# wirelessnode_triac.net
KiCad netlist of a schematic drawn in EAGLE
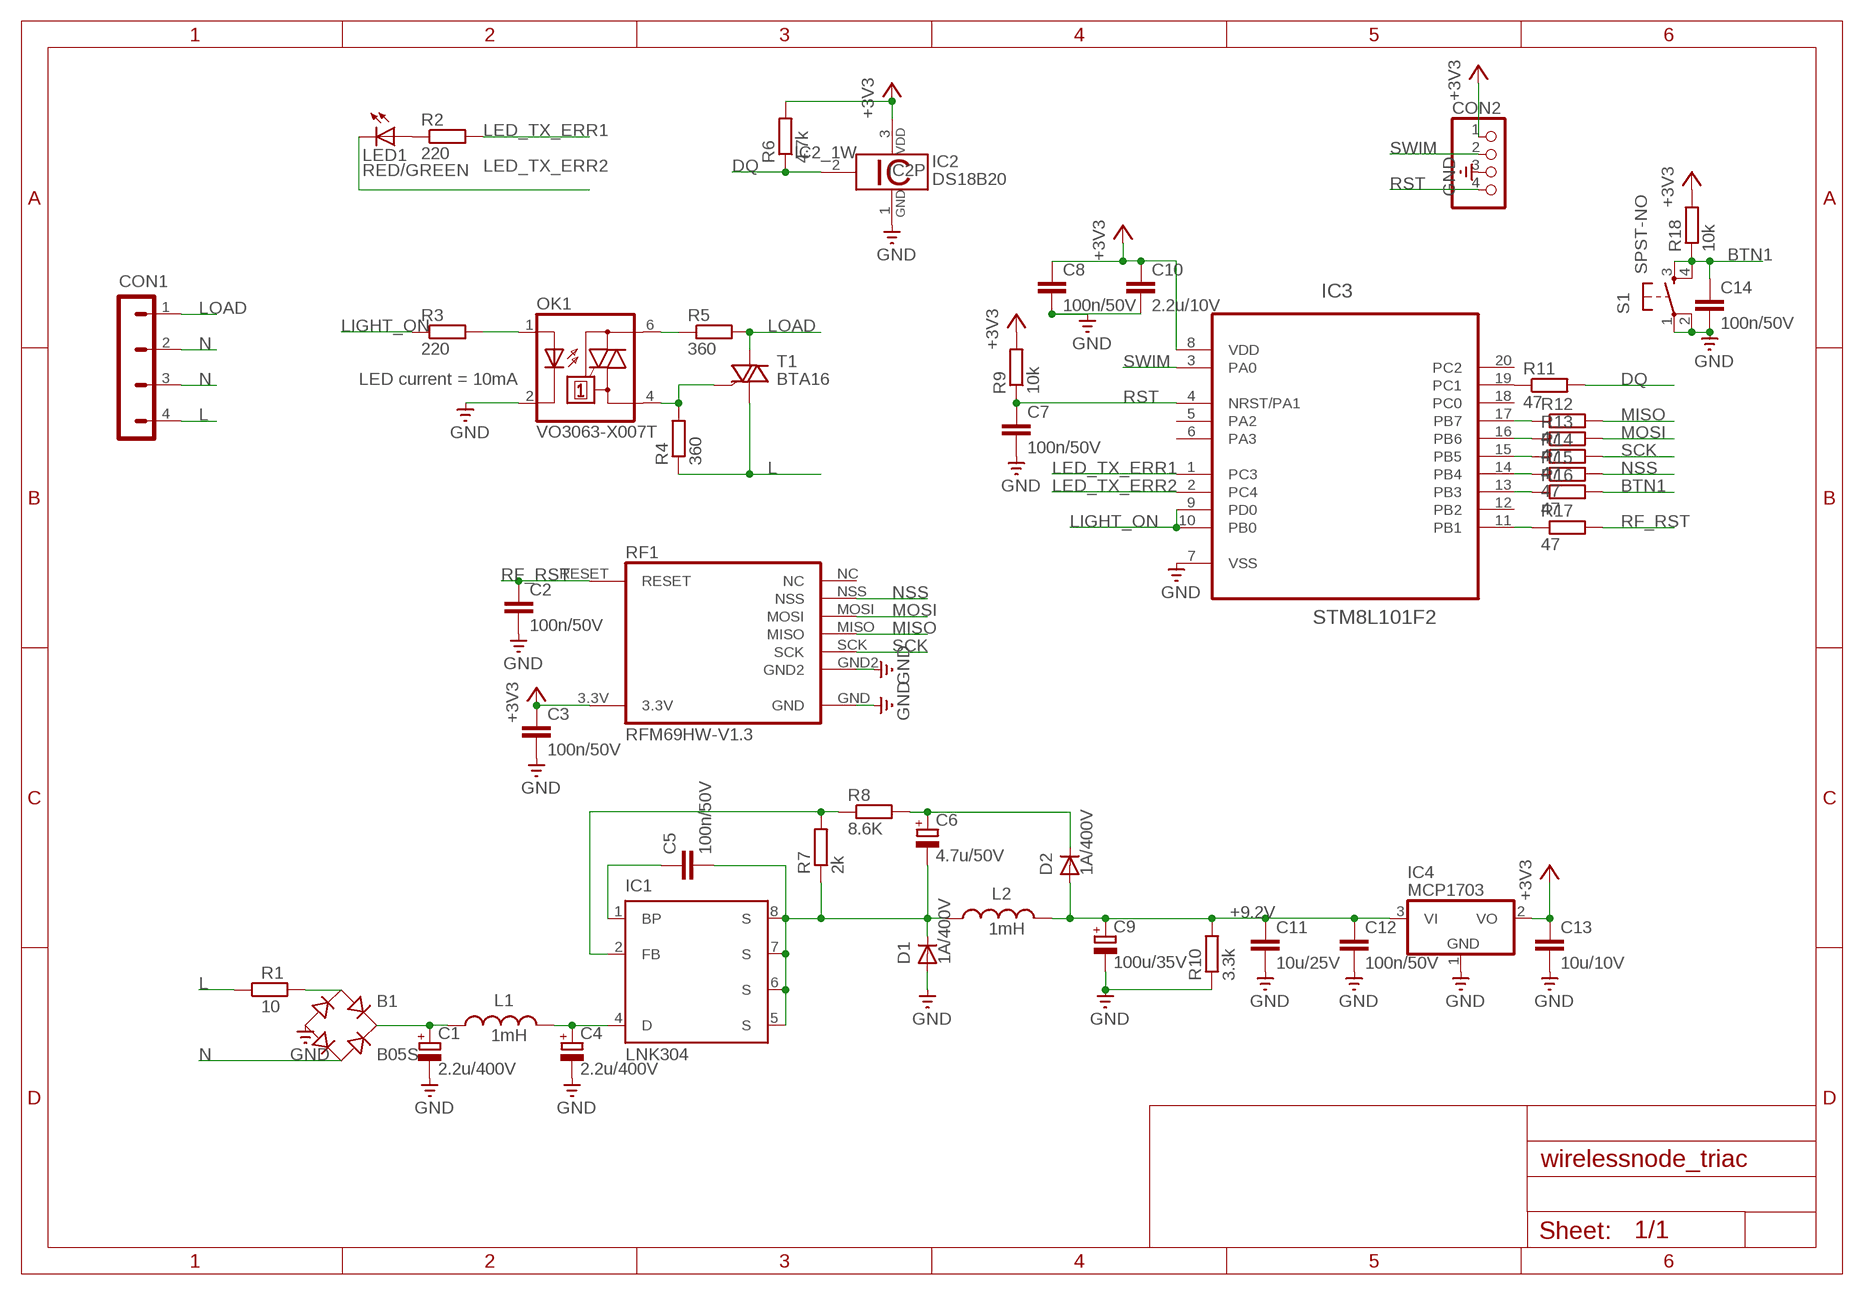
[diagram p0: schematic, sheet 1]

(export (version "E")
  (design (tool "Eeschema 10.0.6"))
  (components
    (comp (ref "B1")
      (value "B05S")
      (footprint "eagle-import:MBS")
      (libsource (lib "eagle-import") (part "BS05"))
    )
    (comp (ref "C1")
      (value "2.2u/400V")
      (footprint "eagle-import:E3.5-8")
      (libsource (lib "eagle-import") (part "C-POL-EUE3.5-8"))
    )
    (comp (ref "C2")
      (value "100n/50V")
      (footprint "eagle-import:C0603K")
      (libsource (lib "eagle-import") (part "C-EUC0603K"))
    )
    (comp (ref "C3")
      (value "100n/50V")
      (footprint "eagle-import:C0603K")
      (libsource (lib "eagle-import") (part "C-EUC0603K"))
    )
    (comp (ref "C4")
      (value "2.2u/400V")
      (footprint "eagle-import:E3.5-8")
      (libsource (lib "eagle-import") (part "C-POL-EUE3.5-8"))
    )
    (comp (ref "C5")
      (value "100n/50V")
      (footprint "eagle-import:C0603K")
      (libsource (lib "eagle-import") (part "C-EUC0603K"))
    )
    (comp (ref "C6")
      (value "4.7u/50V")
      (footprint "eagle-import:PANASONIC_C_LARGER_PADS")
      (libsource (lib "eagle-import") (part "C-POL-EU"))
    )
    (comp (ref "C7")
      (value "100n/50V")
      (footprint "eagle-import:C0603K")
      (libsource (lib "eagle-import") (part "C-EUC0603K"))
    )
    (comp (ref "C8")
      (value "100n/50V")
      (footprint "eagle-import:C0603K")
      (libsource (lib "eagle-import") (part "C-EUC0603K"))
    )
    (comp (ref "C9")
      (value "100u/35V")
      (footprint "eagle-import:PANASONIC_D_LARGER_PADS")
      (libsource (lib "eagle-import") (part "C-POL-EUPANASONIC_D"))
    )
    (comp (ref "C10")
      (value "2.2u/10V")
      (footprint "eagle-import:C0603K")
      (libsource (lib "eagle-import") (part "C-EUC0603K"))
    )
    (comp (ref "C11")
      (value "10u/25V")
      (footprint "eagle-import:C1206")
      (libsource (lib "eagle-import") (part "C-EUC1206"))
    )
    (comp (ref "C12")
      (value "100n/50V")
      (footprint "eagle-import:C0603K")
      (libsource (lib "eagle-import") (part "C-EUC0603K"))
    )
    (comp (ref "C13")
      (value "10u/10V")
      (footprint "eagle-import:C0603K")
      (libsource (lib "eagle-import") (part "C-EUC0603K"))
    )
    (comp (ref "C14")
      (value "100n/50V")
      (footprint "eagle-import:C0603K")
      (libsource (lib "eagle-import") (part "C-EUC0603K"))
    )
    (comp (ref "CON1")
      (value "POWER_CONN_4")
      (footprint "eagle-import:TERMINAL_BLOCK_4")
      (libsource (lib "eagle-import") (part "POWER_CONN_4"))
    )
    (comp (ref "CON2")
      (value "ZL321-4P")
      (footprint "eagle-import:CON_1X4_1.27_SMD")
      (libsource (lib "eagle-import") (part "CON_1X4PIN_1.27MM_SMD"))
    )
    (comp (ref "D1")
      (value "1A/400V")
      (footprint "eagle-import:DO214-AC")
      (libsource (lib "eagle-import") (part "US1G-DIO"))
    )
    (comp (ref "D2")
      (value "1A/400V")
      (footprint "eagle-import:SOD-123F")
      (libsource (lib "eagle-import") (part "SL1G"))
    )
    (comp (ref "IC1")
      (value "LNK304")
      (footprint "eagle-import:SO8_NO_PIN3")
      (libsource (lib "eagle-import") (part "LNK304"))
    )
    (comp (ref "IC2")
      (value "DS18B20")
      (footprint "eagle-import:TO92-")
      (libsource (lib "eagle-import") (part "DS18B20"))
    )
    (comp (ref "IC3")
      (value "STM8L101F2")
      (footprint "eagle-import:TSSOP20")
      (libsource (lib "eagle-import") (part "STM8L101F2"))
    )
    (comp (ref "IC4")
      (value "MCP1703")
      (footprint "eagle-import:SOT23")
      (libsource (lib "eagle-import") (part "MCP1703CB"))
    )
    (comp (ref "L1")
      (value "1mH")
      (footprint "eagle-import:DE0703")
      (libsource (lib "eagle-import") (part "FERROCORE_DE0703-1000"))
    )
    (comp (ref "L2")
      (value "1mH")
      (footprint "eagle-import:DE0703")
      (libsource (lib "eagle-import") (part "FERROCORE_DE0703-1000"))
    )
    (comp (ref "LED1")
      (value "RED/GREEN")
      (footprint "eagle-import:LED5MM")
      (libsource (lib "eagle-import") (part "LED5MM"))
    )
    (comp (ref "OK1")
      (value "VO3063-X007T")
      (footprint "eagle-import:DIL6-SMD")
      (fields (field (name "MF") "FAIRCHILD SEMICONDUCTOR") (field (name "MPN") "MOC3042SM"))
      (libsource (lib "eagle-import") (part "MOC30S42"))
    )
    (comp (ref "R1")
      (value "10")
      (footprint "eagle-import:CF1WS")
      (libsource (lib "eagle-import") (part "R_CF1WS"))
    )
    (comp (ref "R2")
      (value "220")
      (footprint "eagle-import:R0603")
      (libsource (lib "eagle-import") (part "R-EU_R0603"))
    )
    (comp (ref "R3")
      (value "220")
      (footprint "eagle-import:R0603")
      (libsource (lib "eagle-import") (part "R-EU_R0603"))
    )
    (comp (ref "R4")
      (value "360")
      (footprint "eagle-import:R0603")
      (libsource (lib "eagle-import") (part "R-EU_R0603"))
    )
    (comp (ref "R5")
      (value "360")
      (footprint "eagle-import:R0603")
      (libsource (lib "eagle-import") (part "R-EU_R0603"))
    )
    (comp (ref "R6")
      (value "4.7k")
      (footprint "eagle-import:R0603")
      (libsource (lib "eagle-import") (part "R-EU_R0603"))
    )
    (comp (ref "R7")
      (value "2k")
      (footprint "eagle-import:R0603")
      (libsource (lib "eagle-import") (part "R-EU_R0603"))
    )
    (comp (ref "R8")
      (value "8.6K")
      (footprint "eagle-import:R0603")
      (libsource (lib "eagle-import") (part "R-EU_R0603"))
    )
    (comp (ref "R9")
      (value "10k")
      (footprint "eagle-import:R0603")
      (libsource (lib "eagle-import") (part "R-EU_R0603"))
    )
    (comp (ref "R10")
      (value "3.3k")
      (footprint "eagle-import:R0603")
      (libsource (lib "eagle-import") (part "R-EU_R0603"))
    )
    (comp (ref "R11")
      (value "47")
      (footprint "eagle-import:R0603")
      (libsource (lib "eagle-import") (part "R-EU_R0603"))
    )
    (comp (ref "R12")
      (value "47")
      (footprint "eagle-import:R0603")
      (libsource (lib "eagle-import") (part "R-EU_R0603"))
    )
    (comp (ref "R13")
      (value "47")
      (footprint "eagle-import:R0603")
      (libsource (lib "eagle-import") (part "R-EU_R0603"))
    )
    (comp (ref "R14")
      (value "47")
      (footprint "eagle-import:R0603")
      (libsource (lib "eagle-import") (part "R-EU_R0603"))
    )
    (comp (ref "R15")
      (value "47")
      (footprint "eagle-import:R0603")
      (libsource (lib "eagle-import") (part "R-EU_R0603"))
    )
    (comp (ref "R16")
      (value "47")
      (footprint "eagle-import:R0603")
      (libsource (lib "eagle-import") (part "R-EU_R0603"))
    )
    (comp (ref "R17")
      (value "47")
      (footprint "eagle-import:R0603")
      (libsource (lib "eagle-import") (part "R-EU_R0603"))
    )
    (comp (ref "R18")
      (value "10k")
      (footprint "eagle-import:R0603")
      (libsource (lib "eagle-import") (part "R-EU_R0603"))
    )
    (comp (ref "RF1")
      (value "RFM69HW-V1.3")
      (footprint "eagle-import:RFM69HW-V1.3-SMD")
      (libsource (lib "eagle-import") (part "RFM69HW-V1.3"))
    )
    (comp (ref "S1")
      (value "SPST-NO")
      (footprint "eagle-import:DTSM-63X-V-7MM_HEIGHT")
      (libsource (lib "eagle-import") (part "DTSM-63X-V"))
    )
    (comp (ref "T1")
      (value "BTA16")
      (footprint "eagle-import:TO220_SMD")
      (libsource (lib "eagle-import") (part "BT136SMD"))
    )
  )
  (nets
    (net (code "1") (name "+3V3") (class "Default")
      (node (ref "C10") (pin "1") (pinfunction "1_1") (pintype "passive"))
      (node (ref "C13") (pin "1") (pinfunction "1_1") (pintype "passive"))
      (node (ref "C3") (pin "1") (pinfunction "1_1") (pintype "passive"))
      (node (ref "C8") (pin "1") (pinfunction "1_1") (pintype "passive"))
      (node (ref "CON2") (pin "1") (pinfunction "1_1") (pintype "passive"))
      (node (ref "IC2") (pin "3") (pinfunction "VDD_3") (pintype "power_in"))
      (node (ref "IC3") (pin "8") (pinfunction "VDD_8") (pintype "power_in"))
      (node (ref "IC4") (pin "2") (pinfunction "VO_2") (pintype "passive"))
      (node (ref "R18") (pin "2") (pinfunction "2_2") (pintype "passive"))
      (node (ref "R6") (pin "2") (pinfunction "2_2") (pintype "passive"))
      (node (ref "R9") (pin "2") (pinfunction "2_2") (pintype "passive"))
      (node (ref "RF1") (pin "3.3V") (pinfunction "3.3V_3.3V") (pintype "power_in"))
    )
    (net (code "2") (name "/+9.2V") (class "Default")
      (node (ref "C11") (pin "1") (pinfunction "1_1") (pintype "passive"))
      (node (ref "C12") (pin "1") (pinfunction "1_1") (pintype "passive"))
      (node (ref "C9") (pin "+") (pinfunction "+_+") (pintype "passive"))
      (node (ref "D2") (pin "2") (pinfunction "A_2") (pintype "passive"))
      (node (ref "IC4") (pin "3") (pinfunction "VI_3") (pintype "input"))
      (node (ref "L2") (pin "P$2") (pinfunction "2_P$2") (pintype "passive"))
      (node (ref "R10") (pin "2") (pinfunction "2_2") (pintype "passive"))
    )
    (net (code "3") (name "/BTN1") (class "Default")
      (node (ref "C14") (pin "1") (pinfunction "1_1") (pintype "passive"))
      (node (ref "R16") (pin "2") (pinfunction "2_2") (pintype "passive"))
      (node (ref "R18") (pin "1") (pinfunction "1_1") (pintype "passive"))
      (node (ref "S1") (pin "3") (pinfunction "S_3") (pintype "passive"))
      (node (ref "S1") (pin "4") (pinfunction "S1_4") (pintype "passive"))
    )
    (net (code "4") (name "/DQ") (class "Default")
      (node (ref "IC2") (pin "2") (pinfunction "1W_2") (pintype "power_in"))
      (node (ref "R11") (pin "2") (pinfunction "2_2") (pintype "passive"))
      (node (ref "R6") (pin "1") (pinfunction "1_1") (pintype "passive"))
    )
    (net (code "5") (name "/L") (class "Default")
      (node (ref "CON1") (pin "4") (pinfunction "P$4_4") (pintype "bidirectional"))
      (node (ref "R1") (pin "1") (pinfunction "1_1") (pintype "passive"))
      (node (ref "R4") (pin "1") (pinfunction "1_1") (pintype "passive"))
      (node (ref "T1") (pin "1") (pinfunction "A1_1") (pintype "passive"))
    )
    (net (code "6") (name "/LED_TX_ERR1") (class "Default")
      (node (ref "IC3") (pin "1") (pinfunction "PC3_1") (pintype "bidirectional"))
      (node (ref "R2") (pin "2") (pinfunction "2_2") (pintype "passive"))
    )
    (net (code "7") (name "/LED_TX_ERR2") (class "Default")
      (node (ref "IC3") (pin "2") (pinfunction "PC4_2") (pintype "bidirectional"))
      (node (ref "LED1") (pin "K") (pinfunction "C_K") (pintype "passive"))
    )
    (net (code "8") (name "/LIGHT_ON") (class "Default")
      (node (ref "IC3") (pin "10") (pinfunction "PB0_10") (pintype "bidirectional"))
      (node (ref "IC3") (pin "9") (pinfunction "PD0_9") (pintype "bidirectional"))
      (node (ref "R3") (pin "1") (pinfunction "1_1") (pintype "passive"))
    )
    (net (code "9") (name "/LOAD") (class "Default")
      (node (ref "CON1") (pin "1") (pinfunction "P$1_1") (pintype "bidirectional"))
      (node (ref "R5") (pin "2") (pinfunction "2_2") (pintype "passive"))
      (node (ref "T1") (pin "2") (pinfunction "A2_2") (pintype "passive"))
    )
    (net (code "10") (name "/MISO") (class "Default")
      (node (ref "R12") (pin "2") (pinfunction "2_2") (pintype "passive"))
      (node (ref "RF1") (pin "MISO") (pinfunction "MISO_MISO") (pintype "output"))
    )
    (net (code "11") (name "/MOSI") (class "Default")
      (node (ref "R13") (pin "2") (pinfunction "2_2") (pintype "passive"))
      (node (ref "RF1") (pin "MOSI") (pinfunction "MOSI_MOSI") (pintype "output"))
    )
    (net (code "12") (name "/N") (class "Default")
      (node (ref "B1") (pin "AC2") (pinfunction "AC2_AC2") (pintype "passive"))
      (node (ref "CON1") (pin "2") (pinfunction "P$2_2") (pintype "bidirectional"))
      (node (ref "CON1") (pin "3") (pinfunction "P$3_3") (pintype "bidirectional"))
    )
    (net (code "13") (name "/NSS") (class "Default")
      (node (ref "R15") (pin "2") (pinfunction "2_2") (pintype "passive"))
      (node (ref "RF1") (pin "NSS") (pinfunction "NSS_NSS") (pintype "output"))
    )
    (net (code "14") (name "/RF_RST") (class "Default")
      (node (ref "C2") (pin "1") (pinfunction "1_1") (pintype "passive"))
      (node (ref "R17") (pin "2") (pinfunction "2_2") (pintype "passive"))
      (node (ref "RF1") (pin "RESET") (pinfunction "RESET_RESET") (pintype "power_in"))
    )
    (net (code "15") (name "/RST") (class "Default")
      (node (ref "C7") (pin "1") (pinfunction "1_1") (pintype "passive"))
      (node (ref "CON2") (pin "4") (pinfunction "4_4") (pintype "passive"))
      (node (ref "IC3") (pin "4") (pinfunction "NRST/PA1_4") (pintype "bidirectional"))
      (node (ref "R9") (pin "1") (pinfunction "1_1") (pintype "passive"))
    )
    (net (code "16") (name "/SCK") (class "Default")
      (node (ref "R14") (pin "2") (pinfunction "2_2") (pintype "passive"))
      (node (ref "RF1") (pin "SCK") (pinfunction "SCK_SCK") (pintype "output"))
    )
    (net (code "17") (name "/SWIM") (class "Default")
      (node (ref "CON2") (pin "2") (pinfunction "2_2") (pintype "passive"))
      (node (ref "IC3") (pin "3") (pinfunction "PA0_3") (pintype "power_in"))
    )
    (net (code "18") (name "GND") (class "Default")
      (node (ref "B1") (pin "-") (pinfunction "-_-") (pintype "passive"))
      (node (ref "C1") (pin "-") (pinfunction "-_-") (pintype "passive"))
      (node (ref "C10") (pin "2") (pinfunction "2_2") (pintype "passive"))
      (node (ref "C11") (pin "2") (pinfunction "2_2") (pintype "passive"))
      (node (ref "C12") (pin "2") (pinfunction "2_2") (pintype "passive"))
      (node (ref "C13") (pin "2") (pinfunction "2_2") (pintype "passive"))
      (node (ref "C14") (pin "2") (pinfunction "2_2") (pintype "passive"))
      (node (ref "C2") (pin "2") (pinfunction "2_2") (pintype "passive"))
      (node (ref "C3") (pin "2") (pinfunction "2_2") (pintype "passive"))
      (node (ref "C4") (pin "-") (pinfunction "-_-") (pintype "passive"))
      (node (ref "C7") (pin "2") (pinfunction "2_2") (pintype "passive"))
      (node (ref "C8") (pin "2") (pinfunction "2_2") (pintype "passive"))
      (node (ref "C9") (pin "-") (pinfunction "-_-") (pintype "passive"))
      (node (ref "CON2") (pin "3") (pinfunction "3_3") (pintype "passive"))
      (node (ref "D1") (pin "A") (pinfunction "A_A") (pintype "passive"))
      (node (ref "IC2") (pin "1") (pinfunction "GND_1") (pintype "power_in"))
      (node (ref "IC3") (pin "7") (pinfunction "VSS_7") (pintype "power_in"))
      (node (ref "IC4") (pin "1") (pinfunction "GND_1") (pintype "passive"))
      (node (ref "OK1") (pin "2") (pinfunction "C_2") (pintype "passive"))
      (node (ref "R10") (pin "1") (pinfunction "1_1") (pintype "passive"))
      (node (ref "RF1") (pin "GND") (pinfunction "GND_GND") (pintype "input"))
      (node (ref "RF1") (pin "GND2") (pinfunction "GND2_GND2") (pintype "output"))
      (node (ref "S1") (pin "1") (pinfunction "P_1") (pintype "passive"))
      (node (ref "S1") (pin "2") (pinfunction "P1_2") (pintype "passive"))
    )
    (net (code "19") (name "Net-(B1-PadAC1)") (class "Default")
      (node (ref "B1") (pin "AC1") (pinfunction "AC1_AC1") (pintype "passive"))
      (node (ref "R1") (pin "2") (pinfunction "2_2") (pintype "passive"))
    )
    (net (code "20") (name "Net-(D2-C)") (class "Default")
      (node (ref "C6") (pin "+") (pinfunction "+_+") (pintype "passive"))
      (node (ref "D2") (pin "1") (pinfunction "C_1") (pintype "passive"))
      (node (ref "R8") (pin "2") (pinfunction "2_2") (pintype "passive"))
    )
    (net (code "21") (name "Net-(IC1-BP)") (class "Default")
      (node (ref "C5") (pin "1") (pinfunction "1_1") (pintype "passive"))
      (node (ref "IC1") (pin "1") (pinfunction "BP_1") (pintype "power_in"))
    )
    (net (code "22") (name "Net-(IC1-D)") (class "Default")
      (node (ref "C4") (pin "+") (pinfunction "+_+") (pintype "passive"))
      (node (ref "IC1") (pin "4") (pinfunction "D_4") (pintype "power_in"))
      (node (ref "L1") (pin "P$2") (pinfunction "2_P$2") (pintype "passive"))
    )
    (net (code "23") (name "Net-(IC1-FB)") (class "Default")
      (node (ref "IC1") (pin "2") (pinfunction "FB_2") (pintype "input"))
      (node (ref "R7") (pin "2") (pinfunction "2_2") (pintype "passive"))
      (node (ref "R8") (pin "1") (pinfunction "1_1") (pintype "passive"))
    )
    (net (code "24") (name "Net-(IC3-PB1)") (class "Default")
      (node (ref "IC3") (pin "11") (pinfunction "PB1_11") (pintype "bidirectional"))
      (node (ref "R17") (pin "1") (pinfunction "1_1") (pintype "passive"))
    )
    (net (code "25") (name "Net-(IC3-PB3)") (class "Default")
      (node (ref "IC3") (pin "13") (pinfunction "PB3_13") (pintype "bidirectional"))
      (node (ref "R16") (pin "1") (pinfunction "1_1") (pintype "passive"))
    )
    (net (code "26") (name "Net-(IC3-PB4)") (class "Default")
      (node (ref "IC3") (pin "14") (pinfunction "PB4_14") (pintype "bidirectional"))
      (node (ref "R15") (pin "1") (pinfunction "1_1") (pintype "passive"))
    )
    (net (code "27") (name "Net-(IC3-PB5)") (class "Default")
      (node (ref "IC3") (pin "15") (pinfunction "PB5_15") (pintype "bidirectional"))
      (node (ref "R14") (pin "1") (pinfunction "1_1") (pintype "passive"))
    )
    (net (code "28") (name "Net-(IC3-PB6)") (class "Default")
      (node (ref "IC3") (pin "16") (pinfunction "PB6_16") (pintype "bidirectional"))
      (node (ref "R13") (pin "1") (pinfunction "1_1") (pintype "passive"))
    )
    (net (code "29") (name "Net-(IC3-PB7)") (class "Default")
      (node (ref "IC3") (pin "17") (pinfunction "PB7_17") (pintype "bidirectional"))
      (node (ref "R12") (pin "1") (pinfunction "1_1") (pintype "passive"))
    )
    (net (code "30") (name "Net-(IC3-PC1)") (class "Default")
      (node (ref "IC3") (pin "19") (pinfunction "PC1_19") (pintype "bidirectional"))
      (node (ref "R11") (pin "1") (pinfunction "1_1") (pintype "passive"))
    )
    (net (code "31") (name "Net-(L1-1)") (class "Default")
      (node (ref "B1") (pin "+") (pinfunction "+_+") (pintype "passive"))
      (node (ref "C1") (pin "+") (pinfunction "+_+") (pintype "passive"))
      (node (ref "L1") (pin "P$1") (pinfunction "1_P$1") (pintype "passive"))
    )
    (net (code "32") (name "Net-(L2-1)") (class "Default")
      (node (ref "C5") (pin "2") (pinfunction "2_2") (pintype "passive"))
      (node (ref "C6") (pin "-") (pinfunction "-_-") (pintype "passive"))
      (node (ref "D1") (pin "C") (pinfunction "C_C") (pintype "passive"))
      (node (ref "IC1") (pin "5") (pinfunction "S_5") (pintype "power_in"))
      (node (ref "IC1") (pin "6") (pinfunction "S_6") (pintype "power_in"))
      (node (ref "IC1") (pin "7") (pinfunction "S_7") (pintype "power_in"))
      (node (ref "IC1") (pin "8") (pinfunction "S_8") (pintype "power_in"))
      (node (ref "L2") (pin "P$1") (pinfunction "1_P$1") (pintype "passive"))
      (node (ref "R7") (pin "1") (pinfunction "1_1") (pintype "passive"))
    )
    (net (code "33") (name "Net-(LED1-PadA)") (class "Default")
      (node (ref "LED1") (pin "A") (pinfunction "A_A") (pintype "passive"))
      (node (ref "R2") (pin "1") (pinfunction "1_1") (pintype "passive"))
    )
    (net (code "34") (name "Net-(OK1-A)") (class "Default")
      (node (ref "OK1") (pin "1") (pinfunction "A_1") (pintype "passive"))
      (node (ref "R3") (pin "2") (pinfunction "2_2") (pintype "passive"))
    )
    (net (code "35") (name "Net-(OK1-A1)") (class "Default")
      (node (ref "OK1") (pin "4") (pinfunction "A1_4") (pintype "passive"))
      (node (ref "R4") (pin "2") (pinfunction "2_2") (pintype "passive"))
      (node (ref "T1") (pin "3") (pinfunction "G_3") (pintype "passive"))
    )
    (net (code "36") (name "Net-(OK1-A2)") (class "Default")
      (node (ref "OK1") (pin "6") (pinfunction "A2_6") (pintype "passive"))
      (node (ref "R5") (pin "1") (pinfunction "1_1") (pintype "passive"))
    )
    (net (code "37") (name "unconnected-(IC3-PA2-Pad5)") (class "Default")
      (node (ref "IC3") (pin "5") (pinfunction "PA2_5") (pintype "bidirectional"))
    )
    (net (code "38") (name "unconnected-(IC3-PA3-Pad6)") (class "Default")
      (node (ref "IC3") (pin "6") (pinfunction "PA3_6") (pintype "bidirectional"))
    )
    (net (code "39") (name "unconnected-(IC3-PB2-Pad12)") (class "Default")
      (node (ref "IC3") (pin "12") (pinfunction "PB2_12") (pintype "bidirectional"))
    )
    (net (code "40") (name "unconnected-(IC3-PC0-Pad18)") (class "Default")
      (node (ref "IC3") (pin "18") (pinfunction "PC0_18") (pintype "bidirectional"))
    )
    (net (code "41") (name "unconnected-(IC3-PC2-Pad20)") (class "Default")
      (node (ref "IC3") (pin "20") (pinfunction "PC2_20") (pintype "bidirectional"))
    )
    (net (code "42") (name "unconnected-(RF1-PadNC)") (class "Default")
      (node (ref "RF1") (pin "NC") (pinfunction "NC_NC") (pintype "output"))
    )
  )
)
